# appleii.net
KiCad netlist of a schematic drawn in EAGLE
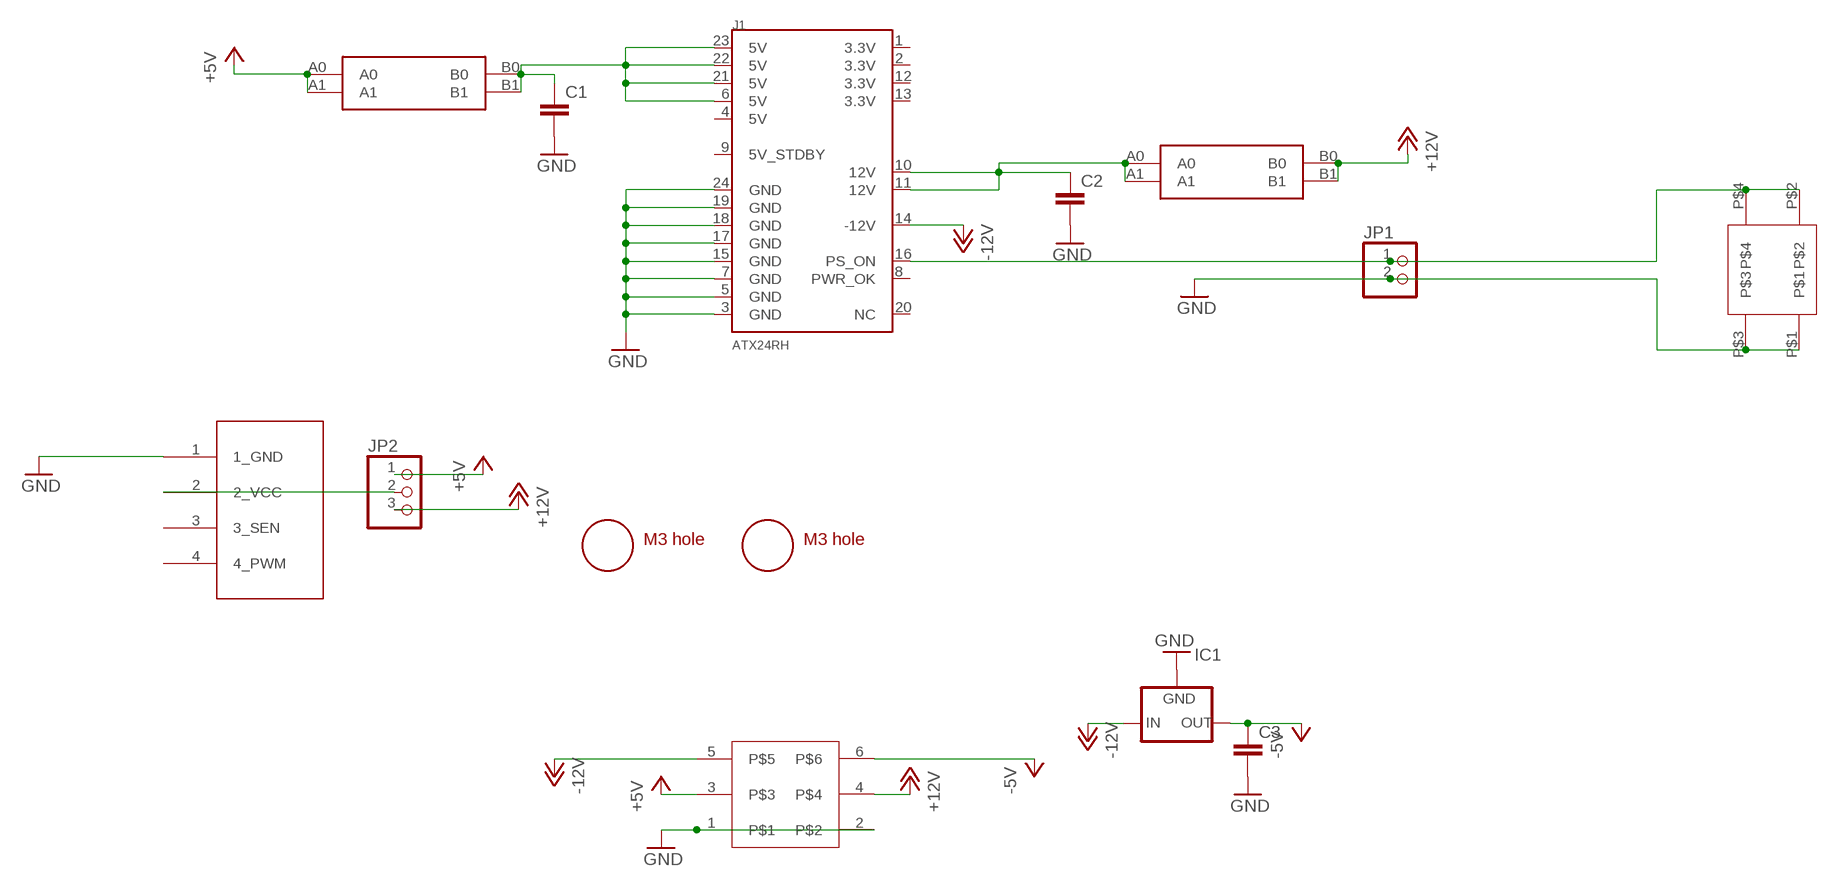
[diagram p0: schematic, sheet 1]

(export (version "E")
  (design (tool "Eeschema 10.0.6"))
  (components
    (comp (ref "C1")
      (value "C5/2.5")
      (footprint "eagle-import:C5B2.5")
      (libsource (lib "eagle-import") (part "C5/2.5"))
    )
    (comp (ref "C2")
      (value "C5/2.5")
      (footprint "eagle-import:C5B2.5")
      (libsource (lib "eagle-import") (part "C5/2.5"))
    )
    (comp (ref "C3")
      (value "C5/2.5")
      (footprint "eagle-import:C5B2.5")
      (libsource (lib "eagle-import") (part "C5/2.5"))
    )
    (comp (ref "IC1")
      (value "79XXS")
      (footprint "eagle-import:79XXS")
      (libsource (lib "eagle-import") (part "79XXS"))
    )
    (comp (ref "J1")
      (value "ATX24RH")
      (footprint "eagle-import:ATX24_RIGHT_ANGLE")
      (libsource (lib "eagle-import") (part "ATX24RH"))
    )
    (comp (ref "JP1")
      (value "PINHD-1X2")
      (footprint "eagle-import:1X02")
      (libsource (lib "eagle-import") (part "PINHD-1X2"))
    )
    (comp (ref "JP2")
      (value "PINHD-1X3")
      (footprint "eagle-import:1X03")
      (libsource (lib "eagle-import") (part "PINHD-1X3"))
    )
    (comp (ref "JP3")
      (value "4PIN_FAN")
      (footprint "eagle-import:1X04")
      (libsource (lib "eagle-import") (part "4PIN_FAN"))
    )
    (comp (ref "U$1")
      (value "CAR_FUSE_HOLDER3IN1")
      (footprint "eagle-import:FUSE_HOLDER_3IN1")
      (libsource (lib "eagle-import") (part "CAR_FUSE_HOLDER3IN1"))
    )
    (comp (ref "U$2")
      (value "CAR_FUSE_HOLDER3IN1")
      (footprint "eagle-import:FUSE_HOLDER_3IN1")
      (libsource (lib "eagle-import") (part "CAR_FUSE_HOLDER3IN1"))
    )
    (comp (ref "U$3")
      (value "ROCK_SW")
      (footprint "eagle-import:ROCK_SWITCH")
      (libsource (lib "eagle-import") (part "ROCK_SW"))
    )
    (comp (ref "U$4")
      (value "M3_MOUNTING_HOLE")
      (footprint "eagle-import:M3_MOUNTING_HOLE_PACK")
      (libsource (lib "eagle-import") (part "M3_MOUNTING_HOLE"))
    )
    (comp (ref "U$5")
      (value "M3_MOUNTING_HOLE")
      (footprint "eagle-import:M3_MOUNTING_HOLE_PACK")
      (libsource (lib "eagle-import") (part "M3_MOUNTING_HOLE"))
    )
    (comp (ref "U$6")
      (value "APPLEII")
      (footprint "eagle-import:APPLEII")
      (libsource (lib "eagle-import") (part "APPLEII"))
    )
  )
  (nets
    (net (code "1") (name "+5V") (class "Default")
      (node (ref "JP2") (pin "1") (pinfunction "1_1") (pintype "passive"))
      (node (ref "U$1") (pin "A0") (pinfunction "A0_A0") (pintype "bidirectional"))
      (node (ref "U$1") (pin "A1") (pinfunction "A1_A1") (pintype "bidirectional"))
      (node (ref "U$6") (pin "3") (pinfunction "P$3_3") (pintype "bidirectional"))
    )
    (net (code "2") (name "+12V") (class "Default")
      (node (ref "JP2") (pin "3") (pinfunction "3_3") (pintype "passive"))
      (node (ref "U$2") (pin "B0") (pinfunction "B0_B0") (pintype "bidirectional"))
      (node (ref "U$2") (pin "B1") (pinfunction "B1_B1") (pintype "bidirectional"))
      (node (ref "U$6") (pin "4") (pinfunction "P$4_4") (pintype "bidirectional"))
    )
    (net (code "3") (name "-5V") (class "Default")
      (node (ref "C3") (pin "1") (pinfunction "1_1") (pintype "passive"))
      (node (ref "IC1") (pin "OUT") (pinfunction "OUT_OUT") (pintype "passive"))
      (node (ref "U$6") (pin "6") (pinfunction "P$6_6") (pintype "bidirectional"))
    )
    (net (code "4") (name "-12V") (class "Default")
      (node (ref "IC1") (pin "IN") (pinfunction "IN_IN") (pintype "input"))
      (node (ref "J1") (pin "14") (pinfunction "-12V_14") (pintype "bidirectional"))
      (node (ref "U$6") (pin "5") (pinfunction "P$5_5") (pintype "bidirectional"))
    )
    (net (code "5") (name "GND") (class "Default")
      (node (ref "C1") (pin "2") (pinfunction "2_2") (pintype "passive"))
      (node (ref "C2") (pin "2") (pinfunction "2_2") (pintype "passive"))
      (node (ref "C3") (pin "2") (pinfunction "2_2") (pintype "passive"))
      (node (ref "IC1") (pin "GND") (pinfunction "GND_GND") (pintype "input"))
      (node (ref "J1") (pin "15") (pinfunction "GND_15") (pintype "bidirectional"))
      (node (ref "J1") (pin "17") (pinfunction "GND_17") (pintype "bidirectional"))
      (node (ref "J1") (pin "18") (pinfunction "GND_18") (pintype "bidirectional"))
      (node (ref "J1") (pin "19") (pinfunction "GND_19") (pintype "bidirectional"))
      (node (ref "J1") (pin "24") (pinfunction "GND_24") (pintype "bidirectional"))
      (node (ref "J1") (pin "3") (pinfunction "GND_3") (pintype "bidirectional"))
      (node (ref "J1") (pin "5") (pinfunction "GND_5") (pintype "bidirectional"))
      (node (ref "J1") (pin "7") (pinfunction "GND_7") (pintype "bidirectional"))
      (node (ref "JP1") (pin "2") (pinfunction "2_2") (pintype "passive"))
      (node (ref "JP3") (pin "1") (pinfunction "1_GND_1") (pintype "passive"))
      (node (ref "U$3") (pin "P$1") (pinfunction "P$1_P$1") (pintype "bidirectional"))
      (node (ref "U$3") (pin "P$3") (pinfunction "P$3_P$3") (pintype "bidirectional"))
      (node (ref "U$6") (pin "1") (pinfunction "P$1_1") (pintype "bidirectional"))
      (node (ref "U$6") (pin "2") (pinfunction "P$2_2") (pintype "bidirectional"))
    )
    (net (code "6") (name "Net-(C1-Pad1)") (class "Default")
      (node (ref "C1") (pin "1") (pinfunction "1_1") (pintype "passive"))
      (node (ref "J1") (pin "21") (pinfunction "5V_21") (pintype "bidirectional"))
      (node (ref "J1") (pin "22") (pinfunction "5V_22") (pintype "bidirectional"))
      (node (ref "J1") (pin "23") (pinfunction "5V_23") (pintype "bidirectional"))
      (node (ref "J1") (pin "6") (pinfunction "5V_6") (pintype "bidirectional"))
      (node (ref "U$1") (pin "B0") (pinfunction "B0_B0") (pintype "bidirectional"))
      (node (ref "U$1") (pin "B1") (pinfunction "B1_B1") (pintype "bidirectional"))
    )
    (net (code "7") (name "Net-(C2-Pad1)") (class "Default")
      (node (ref "C2") (pin "1") (pinfunction "1_1") (pintype "passive"))
      (node (ref "J1") (pin "10") (pinfunction "12V_10") (pintype "bidirectional"))
      (node (ref "J1") (pin "11") (pinfunction "12V_11") (pintype "bidirectional"))
      (node (ref "U$2") (pin "A0") (pinfunction "A0_A0") (pintype "bidirectional"))
      (node (ref "U$2") (pin "A1") (pinfunction "A1_A1") (pintype "bidirectional"))
    )
    (net (code "8") (name "Net-(J1-PS_ON)") (class "Default")
      (node (ref "J1") (pin "16") (pinfunction "PS_ON_16") (pintype "bidirectional"))
      (node (ref "JP1") (pin "1") (pinfunction "1_1") (pintype "passive"))
      (node (ref "U$3") (pin "P$2") (pinfunction "P$2_P$2") (pintype "bidirectional"))
      (node (ref "U$3") (pin "P$4") (pinfunction "P$4_P$4") (pintype "bidirectional"))
    )
    (net (code "9") (name "Net-(JP3-2_VCC)") (class "Default")
      (node (ref "JP2") (pin "2") (pinfunction "2_2") (pintype "passive"))
      (node (ref "JP3") (pin "2") (pinfunction "2_VCC_2") (pintype "passive"))
    )
    (net (code "10") (name "unconnected-(J1-3.3V-Pad1)") (class "Default")
      (node (ref "J1") (pin "1") (pinfunction "3.3V_1") (pintype "bidirectional"))
    )
    (net (code "11") (name "unconnected-(J1-3.3V-Pad2)") (class "Default")
      (node (ref "J1") (pin "2") (pinfunction "3.3V_2") (pintype "bidirectional"))
    )
    (net (code "12") (name "unconnected-(J1-3.3V-Pad12)") (class "Default")
      (node (ref "J1") (pin "12") (pinfunction "3.3V_12") (pintype "bidirectional"))
    )
    (net (code "13") (name "unconnected-(J1-3.3V-Pad13)") (class "Default")
      (node (ref "J1") (pin "13") (pinfunction "3.3V_13") (pintype "bidirectional"))
    )
    (net (code "14") (name "unconnected-(J1-5V-Pad4)") (class "Default")
      (node (ref "J1") (pin "4") (pinfunction "5V_4") (pintype "bidirectional"))
    )
    (net (code "15") (name "unconnected-(J1-5V_STDBY-Pad9)") (class "Default")
      (node (ref "J1") (pin "9") (pinfunction "5V_STDBY_9") (pintype "bidirectional"))
    )
    (net (code "16") (name "unconnected-(J1-NC-Pad20)") (class "Default")
      (node (ref "J1") (pin "20") (pinfunction "NC_20") (pintype "bidirectional"))
    )
    (net (code "17") (name "unconnected-(J1-PWR_OK-Pad8)") (class "Default")
      (node (ref "J1") (pin "8") (pinfunction "PWR_OK_8") (pintype "bidirectional"))
    )
    (net (code "18") (name "unconnected-(JP3-3_SEN-Pad3)") (class "Default")
      (node (ref "JP3") (pin "3") (pinfunction "3_SEN_3") (pintype "passive"))
    )
    (net (code "19") (name "unconnected-(JP3-4_PWM-Pad4)") (class "Default")
      (node (ref "JP3") (pin "4") (pinfunction "4_PWM_4") (pintype "passive"))
    )
  )
)
